# cooler.net
KiCad netlist of a schematic drawn in EAGLE
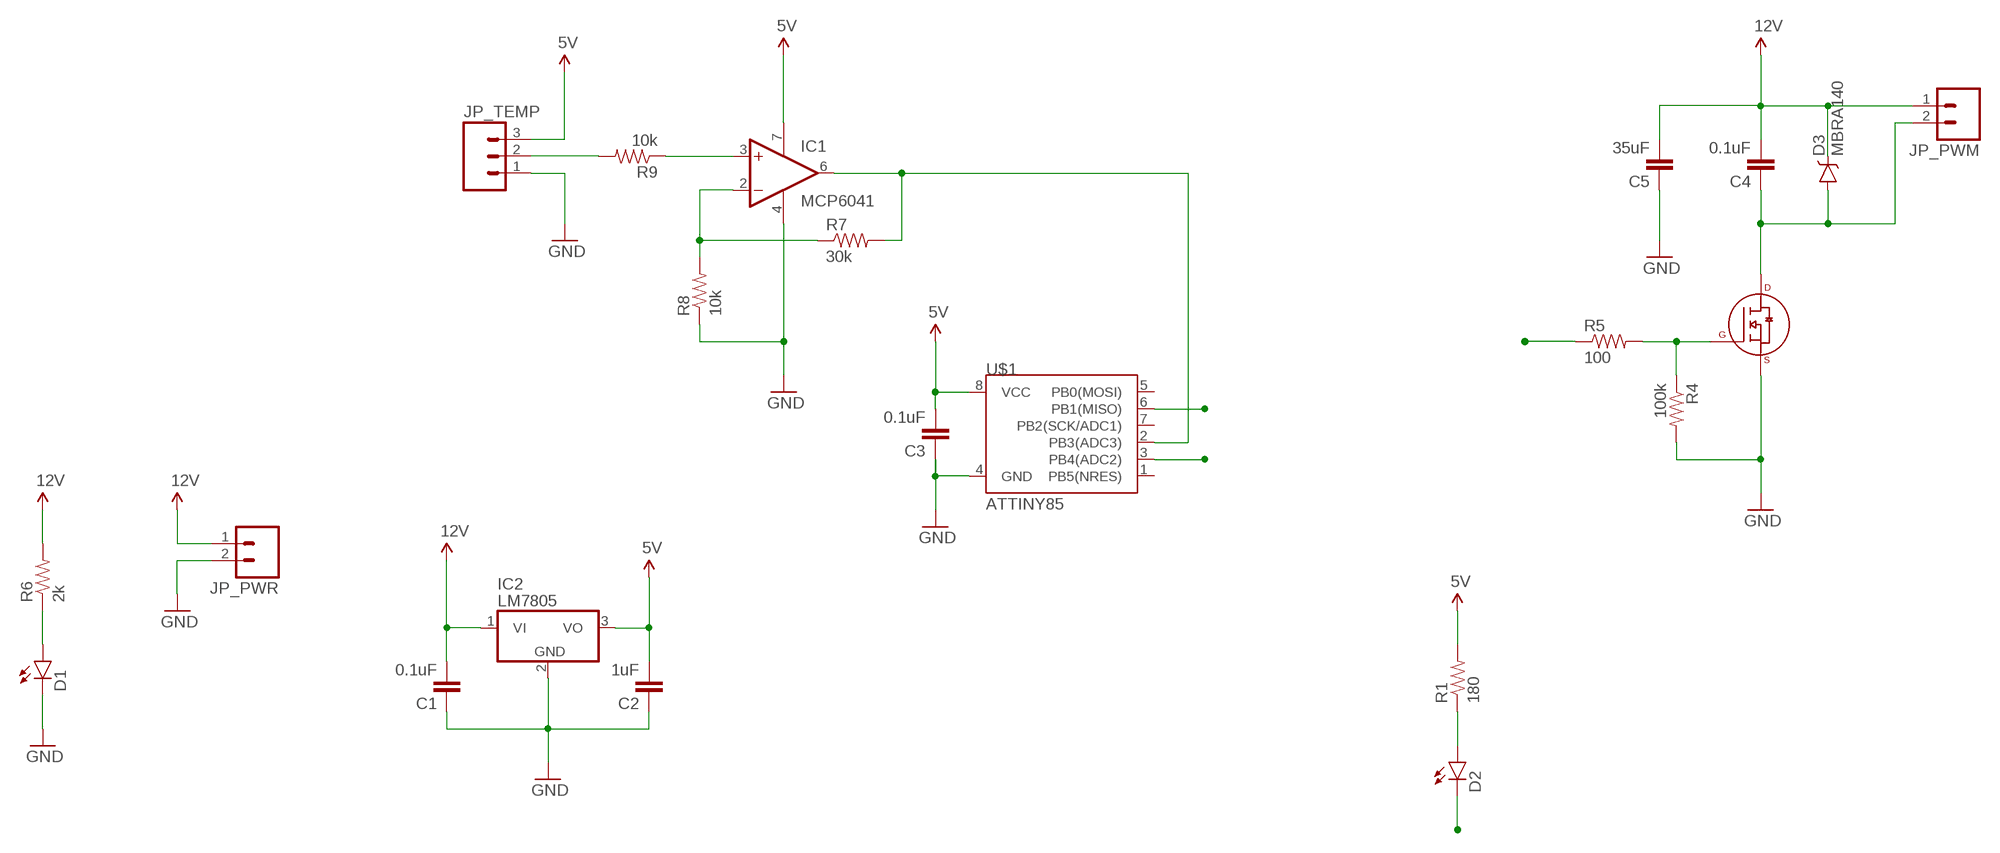
[diagram p0: schematic, sheet 1]

(export (version "E")
  (design (tool "Eeschema 10.0.6"))
  (components
    (comp (ref "C1")
      (value "0.1uF")
      (footprint "eagle-import:1210")
      (libsource (lib "eagle-import") (part "22UF-16V-20%-(1210)"))
    )
    (comp (ref "C2")
      (value "1uF")
      (footprint "eagle-import:1210")
      (libsource (lib "eagle-import") (part "22UF-16V-20%-(1210)"))
    )
    (comp (ref "C3")
      (value "0.1uF")
      (footprint "eagle-import:1210")
      (libsource (lib "eagle-import") (part "22UF-16V-20%-(1210)"))
    )
    (comp (ref "C4")
      (value "0.1uF")
      (footprint "eagle-import:1210")
      (libsource (lib "eagle-import") (part "22UF-16V-20%-(1210)"))
    )
    (comp (ref "C5")
      (value "35uF")
      (footprint "eagle-import:1210")
      (libsource (lib "eagle-import") (part "22UF-16V-20%-(1210)"))
    )
    (comp (ref "D1")
      (value "LED1206")
      (footprint "eagle-import:LED-1206")
      (libsource (lib "eagle-import") (part "LED1206"))
    )
    (comp (ref "D2")
      (value "LED1206")
      (footprint "eagle-import:LED-1206")
      (libsource (lib "eagle-import") (part "LED1206"))
    )
    (comp (ref "D3")
      (value "MBRA140")
      (footprint "eagle-import:SMA-DIODE")
      (libsource (lib "eagle-import") (part "DIODE-SCHOTTKY-MBRA140"))
    )
    (comp (ref "IC1")
      (value "MCP6041")
      (footprint "eagle-import:SO08")
      (libsource (lib "eagle-import") (part "MCP601SN"))
    )
    (comp (ref "IC2")
      (value "LM7805")
      (footprint "eagle-import:TO220V")
      (libsource (lib "eagle-import") (part "78TV05"))
    )
    (comp (ref "JP_PWM")
      (value "M02LOCK_LONGPADS")
      (footprint "eagle-import:1X02_LOCK_LONGPADS")
      (libsource (lib "eagle-import") (part "M02LOCK_LONGPADS"))
    )
    (comp (ref "JP_PWR")
      (value "M02LOCK_LONGPADS")
      (footprint "eagle-import:1X02_LOCK_LONGPADS")
      (libsource (lib "eagle-import") (part "M02LOCK_LONGPADS"))
    )
    (comp (ref "JP_TEMP")
      (value "M03LONGPADS")
      (footprint "eagle-import:1X03_LONGPADS")
      (libsource (lib "eagle-import") (part "M03LONGPADS"))
    )
    (comp (ref "Q2")
      (value "2N7000-2SOT-23")
      (footprint "eagle-import:SOT-23-3")
      (libsource (lib "eagle-import") (part "2N7000-2SOT-23"))
    )
    (comp (ref "R1")
      (value "180")
      (footprint "eagle-import:R2010")
      (libsource (lib "eagle-import") (part "0.11OHM1/2W1%(2010)"))
    )
    (comp (ref "R4")
      (value "100k")
      (footprint "eagle-import:R2010")
      (libsource (lib "eagle-import") (part "0.11OHM1/2W1%(2010)"))
    )
    (comp (ref "R5")
      (value "100")
      (footprint "eagle-import:R2010")
      (libsource (lib "eagle-import") (part "0.11OHM1/2W1%(2010)"))
    )
    (comp (ref "R6")
      (value "2k")
      (footprint "eagle-import:R2010")
      (libsource (lib "eagle-import") (part "0.11OHM1/2W1%(2010)"))
    )
    (comp (ref "R7")
      (value "30k")
      (footprint "eagle-import:R2010")
      (libsource (lib "eagle-import") (part "0.11OHM1/2W1%(2010)"))
    )
    (comp (ref "R8")
      (value "10k")
      (footprint "eagle-import:R2010")
      (libsource (lib "eagle-import") (part "0.11OHM1/2W1%(2010)"))
    )
    (comp (ref "R9")
      (value "10k")
      (footprint "eagle-import:R2010")
      (libsource (lib "eagle-import") (part "0.11OHM1/2W1%(2010)"))
    )
    (comp (ref "U$1")
      (value "ATTINY85")
      (footprint "eagle-import:SO08")
      (libsource (lib "eagle-import") (part "ATTINY13SOIC"))
    )
  )
  (nets
    (net (code "1") (name "/LED") (class "Default")
      (node (ref "D2") (pin "C") (pinfunction "C_C") (pintype "passive"))
      (node (ref "U$1") (pin "3") (pinfunction "PB4(ADC2)_3") (pintype "bidirectional"))
    )
    (net (code "2") (name "/PWM") (class "Default")
      (node (ref "R5") (pin "1") (pinfunction "1_1") (pintype "passive"))
      (node (ref "U$1") (pin "6") (pinfunction "PB1(MISO)_6") (pintype "bidirectional"))
    )
    (net (code "3") (name "5V") (class "Default")
      (node (ref "C2") (pin "2") (pinfunction "2_2") (pintype "passive"))
      (node (ref "C3") (pin "2") (pinfunction "2_2") (pintype "passive"))
      (node (ref "IC1") (pin "7") (pinfunction "V+_7") (pintype "power_in"))
      (node (ref "IC2") (pin "3") (pinfunction "VO_3") (pintype "passive"))
      (node (ref "JP_TEMP") (pin "3") (pinfunction "3_3") (pintype "passive"))
      (node (ref "R1") (pin "2") (pinfunction "2_2") (pintype "passive"))
      (node (ref "U$1") (pin "8") (pinfunction "VCC_8") (pintype "bidirectional"))
    )
    (net (code "4") (name "12V") (class "Default")
      (node (ref "C1") (pin "2") (pinfunction "2_2") (pintype "passive"))
      (node (ref "C4") (pin "2") (pinfunction "2_2") (pintype "passive"))
      (node (ref "C5") (pin "2") (pinfunction "2_2") (pintype "passive"))
      (node (ref "D3") (pin "C") (pinfunction "C_C") (pintype "passive"))
      (node (ref "IC2") (pin "1") (pinfunction "VI_1") (pintype "input"))
      (node (ref "JP_PWM") (pin "1") (pinfunction "1_1") (pintype "passive"))
      (node (ref "JP_PWR") (pin "1") (pinfunction "1_1") (pintype "passive"))
      (node (ref "R6") (pin "2") (pinfunction "2_2") (pintype "passive"))
    )
    (net (code "5") (name "GND") (class "Default")
      (node (ref "C1") (pin "1") (pinfunction "1_1") (pintype "passive"))
      (node (ref "C2") (pin "1") (pinfunction "1_1") (pintype "passive"))
      (node (ref "C3") (pin "1") (pinfunction "1_1") (pintype "passive"))
      (node (ref "C5") (pin "1") (pinfunction "1_1") (pintype "passive"))
      (node (ref "D1") (pin "C") (pinfunction "C_C") (pintype "passive"))
      (node (ref "IC1") (pin "4") (pinfunction "V-_4") (pintype "power_in"))
      (node (ref "IC2") (pin "2") (pinfunction "GND_2") (pintype "passive"))
      (node (ref "JP_PWR") (pin "2") (pinfunction "2_2") (pintype "passive"))
      (node (ref "JP_TEMP") (pin "1") (pinfunction "1_1") (pintype "passive"))
      (node (ref "Q2") (pin "2") (pinfunction "S_2") (pintype "bidirectional"))
      (node (ref "R4") (pin "2") (pinfunction "2_2") (pintype "passive"))
      (node (ref "R8") (pin "1") (pinfunction "1_1") (pintype "passive"))
      (node (ref "U$1") (pin "4") (pinfunction "GND_4") (pintype "bidirectional"))
    )
    (net (code "6") (name "Net-(D1-PadA)") (class "Default")
      (node (ref "D1") (pin "A") (pinfunction "A_A") (pintype "passive"))
      (node (ref "R6") (pin "1") (pinfunction "1_1") (pintype "passive"))
    )
    (net (code "7") (name "Net-(D2-PadA)") (class "Default")
      (node (ref "D2") (pin "A") (pinfunction "A_A") (pintype "passive"))
      (node (ref "R1") (pin "1") (pinfunction "1_1") (pintype "passive"))
    )
    (net (code "8") (name "Net-(IC1-+IN)") (class "Default")
      (node (ref "IC1") (pin "3") (pinfunction "+IN_3") (pintype "input"))
      (node (ref "R9") (pin "1") (pinfunction "1_1") (pintype "passive"))
    )
    (net (code "9") (name "Net-(IC1--IN)") (class "Default")
      (node (ref "IC1") (pin "2") (pinfunction "-IN_2") (pintype "input"))
      (node (ref "R7") (pin "1") (pinfunction "1_1") (pintype "passive"))
      (node (ref "R8") (pin "2") (pinfunction "2_2") (pintype "passive"))
    )
    (net (code "10") (name "Net-(IC1-OUT)") (class "Default")
      (node (ref "IC1") (pin "6") (pinfunction "OUT_6") (pintype "output"))
      (node (ref "R7") (pin "2") (pinfunction "2_2") (pintype "passive"))
      (node (ref "U$1") (pin "2") (pinfunction "PB3(ADC3)_2") (pintype "bidirectional"))
    )
    (net (code "11") (name "Net-(JP_TEMP-Pad2)") (class "Default")
      (node (ref "JP_TEMP") (pin "2") (pinfunction "2_2") (pintype "passive"))
      (node (ref "R9") (pin "2") (pinfunction "2_2") (pintype "passive"))
    )
    (net (code "12") (name "Net-(Q2-D)") (class "Default")
      (node (ref "C4") (pin "1") (pinfunction "1_1") (pintype "passive"))
      (node (ref "D3") (pin "A") (pinfunction "A_A") (pintype "passive"))
      (node (ref "JP_PWM") (pin "2") (pinfunction "2_2") (pintype "passive"))
      (node (ref "Q2") (pin "3") (pinfunction "D_3") (pintype "bidirectional"))
    )
    (net (code "13") (name "Net-(Q2-G)") (class "Default")
      (node (ref "Q2") (pin "1") (pinfunction "G_1") (pintype "bidirectional"))
      (node (ref "R4") (pin "1") (pinfunction "1_1") (pintype "passive"))
      (node (ref "R5") (pin "2") (pinfunction "2_2") (pintype "passive"))
    )
    (net (code "14") (name "unconnected-(U$1-PB0(MOSI)-Pad5)") (class "Default")
      (node (ref "U$1") (pin "5") (pinfunction "PB0(MOSI)_5") (pintype "bidirectional"))
    )
    (net (code "15") (name "unconnected-(U$1-PB2(SCK{slash}ADC1)-Pad7)") (class "Default")
      (node (ref "U$1") (pin "7") (pinfunction "PB2(SCK/ADC1)_7") (pintype "bidirectional"))
    )
    (net (code "16") (name "unconnected-(U$1-PB5(NRES)-Pad1)") (class "Default")
      (node (ref "U$1") (pin "1") (pinfunction "PB5(NRES)_1") (pintype "bidirectional"))
    )
  )
)
